# TOP.net
KiCad netlist of a schematic drawn in Altium Designer
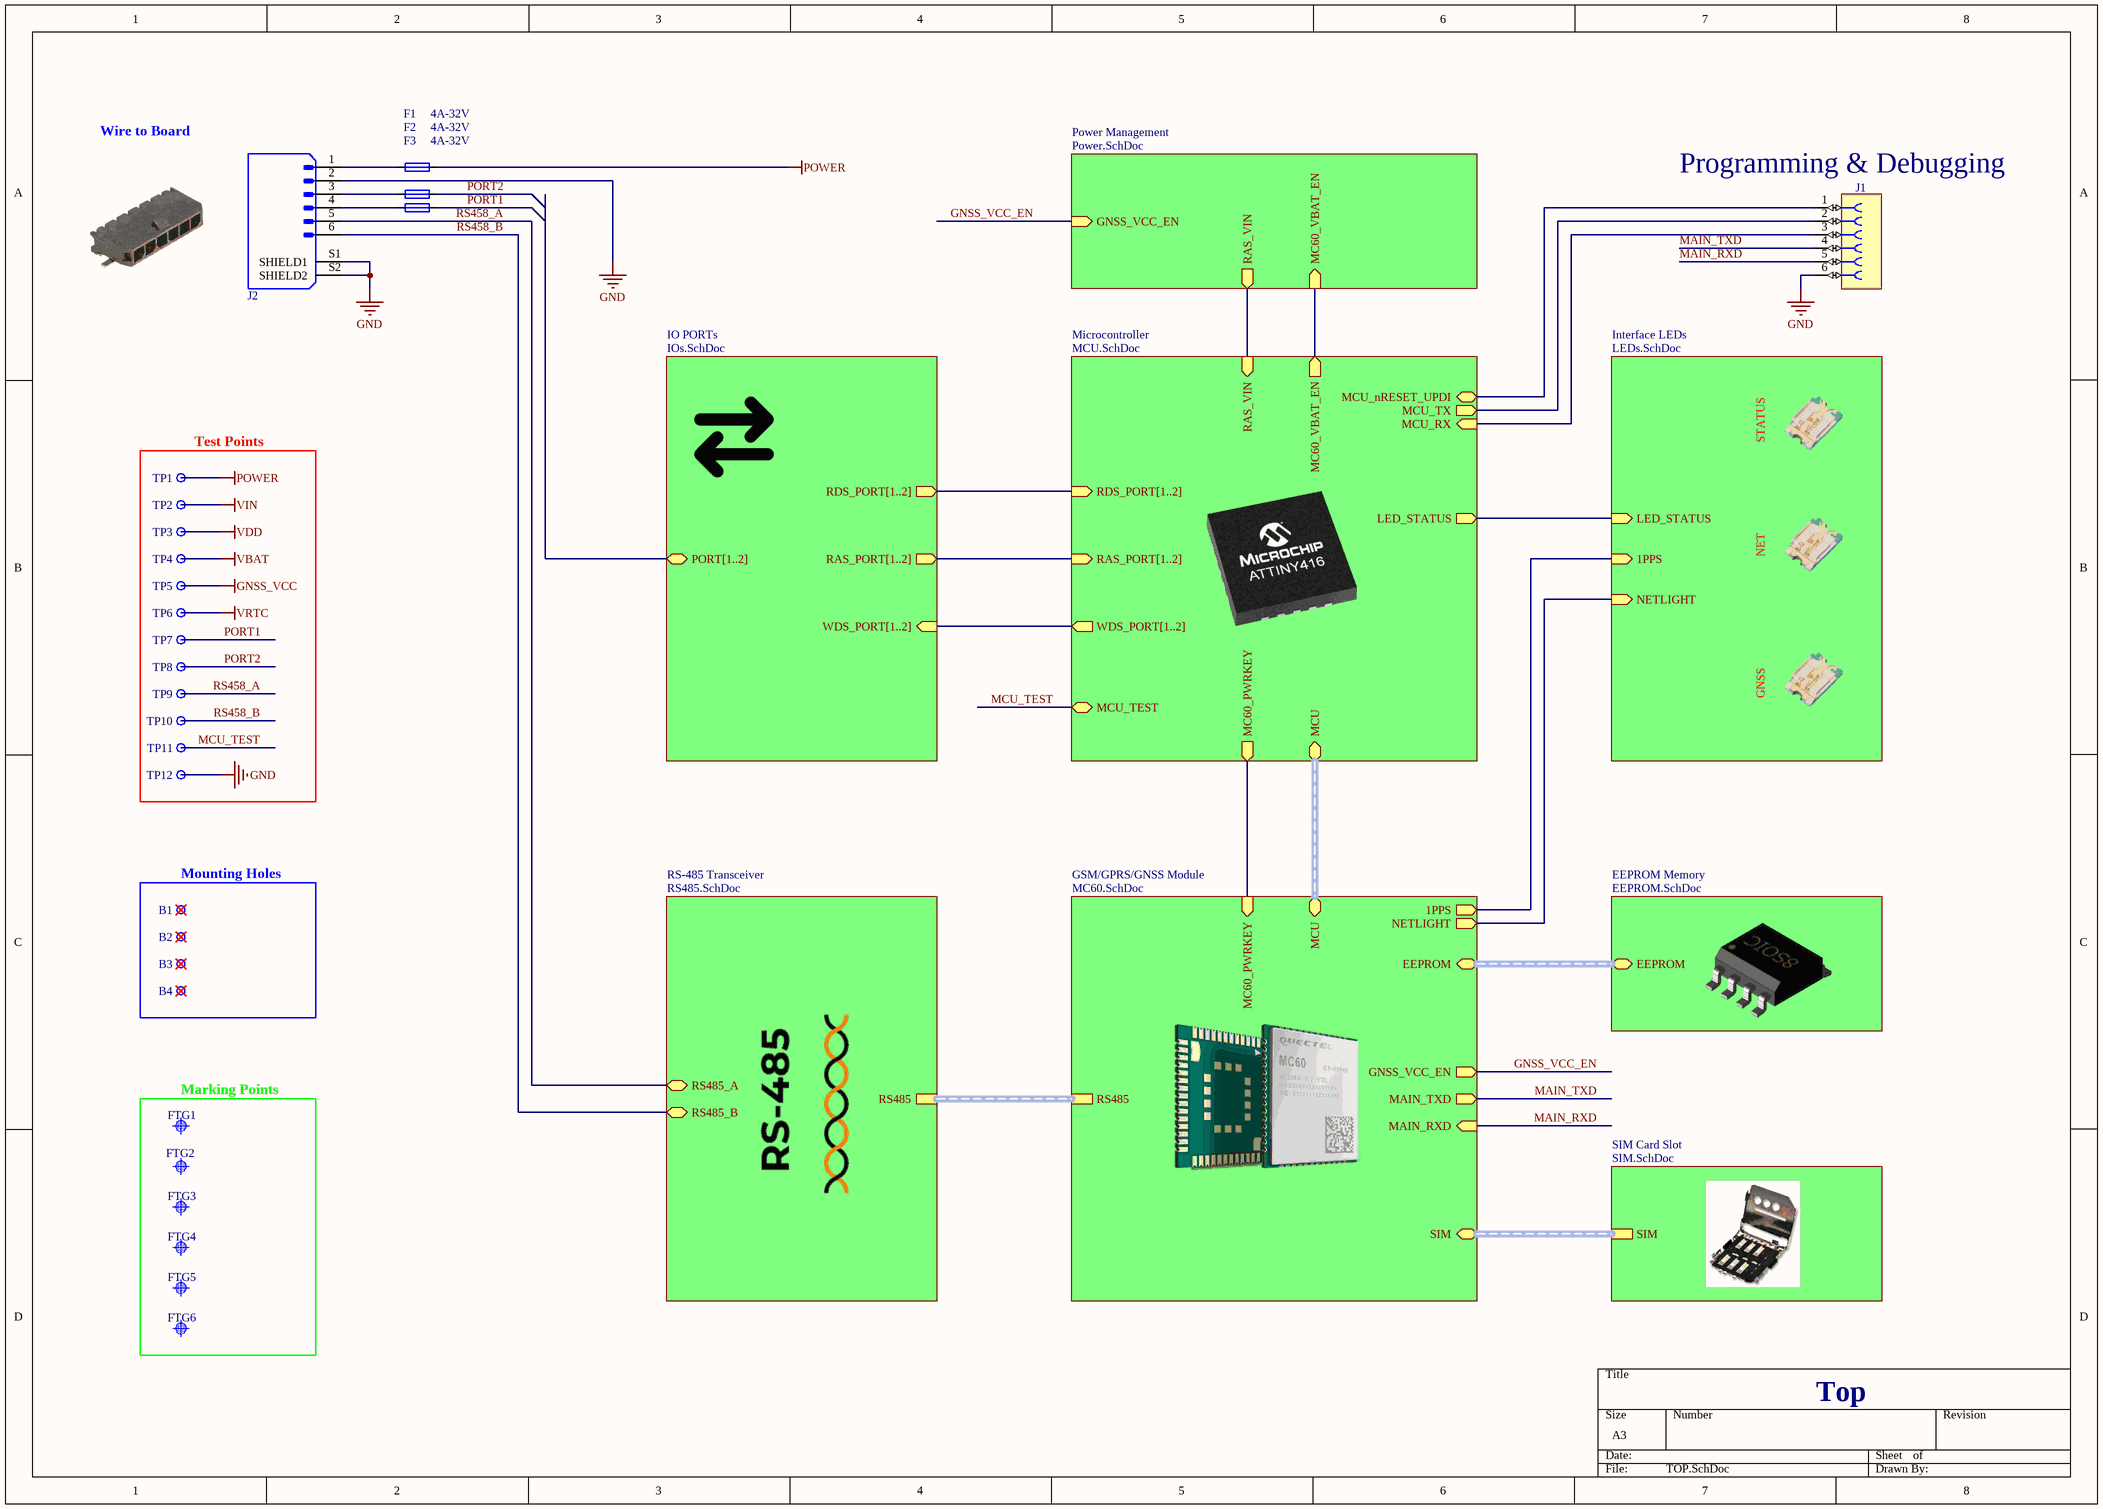
[diagram p0: TOP.SchDoc]

(export (version "E")
  (design (tool "Eeschema 10.0.6"))
  (components
    (comp (ref "B1")
      (value "Non Plated Hole")
      (footprint "MTG520")
      (description "Single Terminal Socket")
      (fields (field (name "PART NUMBER") "NON-PLATED_HOLE5.2") (field (name "AUTHOR") "CERN DEM JMW"))
      (libsource (lib "Eletro-mechanical") (part "Single Terminal Socket"))
    )
    (comp (ref "B2")
      (value "Non Plated Hole")
      (footprint "MTG520")
      (description "Single Terminal Socket")
      (fields (field (name "PART NUMBER") "NON-PLATED_HOLE5.2") (field (name "AUTHOR") "CERN DEM JMW"))
      (libsource (lib "Eletro-mechanical") (part "Single Terminal Socket"))
    )
    (comp (ref "B3")
      (value "Non Plated Hole")
      (footprint "MTG520")
      (description "Single Terminal Socket")
      (fields (field (name "PART NUMBER") "NON-PLATED_HOLE5.2") (field (name "AUTHOR") "CERN DEM JMW"))
      (libsource (lib "Eletro-mechanical") (part "Single Terminal Socket"))
    )
    (comp (ref "B4")
      (value "Non Plated Hole")
      (footprint "MTG520")
      (description "Single Terminal Socket")
      (fields (field (name "PART NUMBER") "NON-PLATED_HOLE5.2") (field (name "AUTHOR") "CERN DEM JMW"))
      (libsource (lib "Eletro-mechanical") (part "Single Terminal Socket"))
    )
    (comp (ref "F1")
      (value "4A-32V")
      (footprint "FUSC_LITTELFUSE_466")
      (description "Fuse")
      (fields
        (field (name "PART NUMBER") "FUS1206_LITTELFUSE_0466004.NR")
        (field (name "MANUFACTURER") "LITTELFUSE")
        (field (name "AUTHOR") "CERN DEM BC")
      )
      (libsource (lib "Eletro-mechanical") (part "Fuse"))
    )
    (comp (ref "F2")
      (value "4A-32V")
      (footprint "FUSC_LITTELFUSE_466")
      (description "Fuse")
      (fields
        (field (name "PART NUMBER") "FUS1206_LITTELFUSE_0466004.NR")
        (field (name "MANUFACTURER") "LITTELFUSE")
        (field (name "AUTHOR") "CERN DEM BC")
      )
      (libsource (lib "Eletro-mechanical") (part "Fuse"))
    )
    (comp (ref "F3")
      (value "4A-32V")
      (footprint "FUSC_LITTELFUSE_466")
      (description "Fuse")
      (fields
        (field (name "PART NUMBER") "FUS1206_LITTELFUSE_0466004.NR")
        (field (name "MANUFACTURER") "LITTELFUSE")
        (field (name "AUTHOR") "CERN DEM BC")
      )
      (libsource (lib "Eletro-mechanical") (part "Fuse"))
    )
    (comp (ref "FTG1")
      (value "Use only in PCB")
      (footprint "FIDUCIAL_TOP_C100-200")
      (description "Fiducial Target")
      (fields (field (name "PART NUMBER") "FIDUCIAL_TARGET_C100-200") (field (name "AUTHOR") "CERN DEM JLC"))
      (libsource (lib "Eletro-mechanical") (part "Fiducial Target"))
    )
    (comp (ref "FTG2")
      (value "Use only in PCB")
      (footprint "FIDUCIAL_TOP_C100-200")
      (description "Fiducial Target")
      (fields (field (name "PART NUMBER") "FIDUCIAL_TARGET_C100-200") (field (name "AUTHOR") "CERN DEM JLC"))
      (libsource (lib "Eletro-mechanical") (part "Fiducial Target"))
    )
    (comp (ref "FTG3")
      (value "Use only in PCB")
      (footprint "FIDUCIAL_TOP_C100-200")
      (description "Fiducial Target")
      (fields (field (name "PART NUMBER") "FIDUCIAL_TARGET_C100-200") (field (name "AUTHOR") "CERN DEM JLC"))
      (libsource (lib "Eletro-mechanical") (part "Fiducial Target"))
    )
    (comp (ref "FTG4")
      (value "Use only in PCB")
      (footprint "FIDUCIAL_TOP_C100-200")
      (description "Fiducial Target")
      (fields (field (name "PART NUMBER") "FIDUCIAL_TARGET_C100-200") (field (name "AUTHOR") "CERN DEM JLC"))
      (libsource (lib "Eletro-mechanical") (part "Fiducial Target"))
    )
    (comp (ref "FTG5")
      (value "Use only in PCB")
      (footprint "FIDUCIAL_TOP_C100-200")
      (description "Fiducial Target")
      (fields (field (name "PART NUMBER") "FIDUCIAL_TARGET_C100-200") (field (name "AUTHOR") "CERN DEM JLC"))
      (libsource (lib "Eletro-mechanical") (part "Fiducial Target"))
    )
    (comp (ref "FTG6")
      (value "Use only in PCB")
      (footprint "FIDUCIAL_TOP_C100-200")
      (description "Fiducial Target")
      (fields (field (name "PART NUMBER") "FIDUCIAL_TARGET_C100-200") (field (name "AUTHOR") "CERN DEM JLC"))
      (libsource (lib "Eletro-mechanical") (part "Fiducial Target"))
    )
    (comp (ref "J1")
      (value "Socket 6")
      (footprint "SAMTEC_SSW-106-01-L-S")
      (description "Connector 6 Female")
      (fields
        (field (name "PART NUMBER") "SAMTEC_SSW-106-01-L-S")
        (field (name "MANUFACTURER") "OPEN")
        (field (name "AUTHOR") "CERN DEM BC")
      )
      (libsource (lib "Connectors") (part "Connector 6 Female"))
    )
    (comp (ref "J2")
      (value "43650-0613")
      (footprint "MOLEX_43650-0613")
      (description "Connector Header Surface Mount, Right Angle 6 position 0.118\" (3.00mm)")
      (fields
        (field (name "MP") "436500613")
        (field (name "PART NUMBER") "MOLEX_43650-0613")
        (field (name "AUTHOR") "Xusniyor")
      )
      (libsource (lib "Connectors") (part "MOLEX_43650-0613"))
    )
    (comp (ref "TP1")
      (value "Test Point")
      (footprint "TPS127")
      (fields (field (name "PART NUMBER") "SMD_PAD_1.27X1.27MM") (field (name "AUTHOR") "CERN DEM JLC"))
      (libsource (lib "Eletro-mechanical") (part "Test Point"))
    )
    (comp (ref "TP2")
      (value "Test Point")
      (footprint "TPS127")
      (fields (field (name "PART NUMBER") "SMD_PAD_1.27X1.27MM") (field (name "AUTHOR") "CERN DEM JLC"))
      (libsource (lib "Eletro-mechanical") (part "Test Point"))
    )
    (comp (ref "TP3")
      (value "Test Point")
      (footprint "TPS127")
      (fields (field (name "PART NUMBER") "SMD_PAD_1.27X1.27MM") (field (name "AUTHOR") "CERN DEM JLC"))
      (libsource (lib "Eletro-mechanical") (part "Test Point"))
    )
    (comp (ref "TP4")
      (value "Test Point")
      (footprint "TPS127")
      (fields (field (name "PART NUMBER") "SMD_PAD_1.27X1.27MM") (field (name "AUTHOR") "CERN DEM JLC"))
      (libsource (lib "Eletro-mechanical") (part "Test Point"))
    )
    (comp (ref "TP5")
      (value "Test Point")
      (footprint "TPS127")
      (fields (field (name "PART NUMBER") "SMD_PAD_1.27X1.27MM") (field (name "AUTHOR") "CERN DEM JLC"))
      (libsource (lib "Eletro-mechanical") (part "Test Point"))
    )
    (comp (ref "TP6")
      (value "Test Point")
      (footprint "TPS127")
      (fields (field (name "PART NUMBER") "SMD_PAD_1.27X1.27MM") (field (name "AUTHOR") "CERN DEM JLC"))
      (libsource (lib "Eletro-mechanical") (part "Test Point"))
    )
    (comp (ref "TP7")
      (value "Test Point")
      (footprint "TPS127")
      (fields (field (name "PART NUMBER") "SMD_PAD_1.27X1.27MM") (field (name "AUTHOR") "CERN DEM JLC"))
      (libsource (lib "Eletro-mechanical") (part "Test Point"))
    )
    (comp (ref "TP8")
      (value "Test Point")
      (footprint "TPS127")
      (fields (field (name "PART NUMBER") "SMD_PAD_1.27X1.27MM") (field (name "AUTHOR") "CERN DEM JLC"))
      (libsource (lib "Eletro-mechanical") (part "Test Point"))
    )
    (comp (ref "TP9")
      (value "Test Point")
      (footprint "TPS127")
      (fields (field (name "PART NUMBER") "SMD_PAD_1.27X1.27MM") (field (name "AUTHOR") "CERN DEM JLC"))
      (libsource (lib "Eletro-mechanical") (part "Test Point"))
    )
    (comp (ref "TP10")
      (value "Test Point")
      (footprint "TPS127")
      (fields (field (name "PART NUMBER") "SMD_PAD_1.27X1.27MM") (field (name "AUTHOR") "CERN DEM JLC"))
      (libsource (lib "Eletro-mechanical") (part "Test Point"))
    )
    (comp (ref "TP11")
      (value "Test Point")
      (footprint "TPS127")
      (fields (field (name "PART NUMBER") "SMD_PAD_1.27X1.27MM") (field (name "AUTHOR") "CERN DEM JLC"))
      (libsource (lib "Eletro-mechanical") (part "Test Point"))
    )
    (comp (ref "TP12")
      (value "Test Point")
      (footprint "TPS127")
      (fields (field (name "PART NUMBER") "SMD_PAD_1.27X1.27MM") (field (name "AUTHOR") "CERN DEM JLC"))
      (libsource (lib "Eletro-mechanical") (part "Test Point"))
    )
  )
  (nets
    (net (code "5") (name "/MAIN_RXD") (class "Default")
      (node (ref "J1") (pin "5") (pinfunction "5_5") (pintype "bidirectional"))
    )
    (net (code "6") (name "/MAIN_TXD") (class "Default")
      (node (ref "J1") (pin "4") (pinfunction "4_4") (pintype "bidirectional"))
    )
    (net (code "9") (name "/MCU_RX") (class "Default")
      (node (ref "J1") (pin "3") (pinfunction "3_3") (pintype "bidirectional"))
    )
    (net (code "10") (name "/MCU_TEST") (class "Default")
      (node (ref "TP11") (pin "1") (pinfunction "1_1") (pintype "bidirectional"))
    )
    (net (code "11") (name "/MCU_TX") (class "Default")
      (node (ref "J1") (pin "2") (pinfunction "2_2") (pintype "bidirectional"))
    )
    (net (code "12") (name "/MCU_nRESET_UPDI") (class "Default")
      (node (ref "J1") (pin "1") (pinfunction "1_1") (pintype "bidirectional"))
    )
    (net (code "15") (name "/PORT1") (class "Default")
      (node (ref "F3") (pin "2") (pinfunction "2_2") (pintype "passive"))
      (node (ref "TP7") (pin "1") (pinfunction "1_1") (pintype "bidirectional"))
    )
    (net (code "16") (name "/PORT2") (class "Default")
      (node (ref "F2") (pin "2") (pinfunction "2_2") (pintype "passive"))
      (node (ref "TP8") (pin "1") (pinfunction "1_1") (pintype "bidirectional"))
    )
    (net (code "21") (name "/RS458_A") (class "Default")
      (node (ref "J2") (pin "5") (pinfunction "5_5") (pintype "passive"))
      (node (ref "TP9") (pin "1") (pinfunction "1_1") (pintype "bidirectional"))
    )
    (net (code "22") (name "/RS458_B") (class "Default")
      (node (ref "J2") (pin "6") (pinfunction "6_6") (pintype "passive"))
      (node (ref "TP10") (pin "1") (pinfunction "1_1") (pintype "bidirectional"))
    )
    (net (code "26") (name "GND") (class "Default")
      (node (ref "J1") (pin "6") (pinfunction "6_6") (pintype "bidirectional"))
      (node (ref "J2") (pin "2") (pinfunction "2_2") (pintype "passive"))
      (node (ref "J2") (pin "S1") (pinfunction "SHIELD1_S1") (pintype "passive"))
      (node (ref "J2") (pin "S2") (pinfunction "SHIELD2_S2") (pintype "passive"))
      (node (ref "TP12") (pin "1") (pinfunction "1_1") (pintype "bidirectional"))
    )
    (net (code "27") (name "GNSS_VCC") (class "Default")
      (node (ref "TP5") (pin "1") (pinfunction "1_1") (pintype "bidirectional"))
    )
    (net (code "28") (name "Net-(F1-Pad1)") (class "Default")
      (node (ref "F1") (pin "1") (pinfunction "1_1") (pintype "passive"))
      (node (ref "J2") (pin "1") (pinfunction "1_1") (pintype "passive"))
    )
    (net (code "29") (name "Net-(F2-Pad1)") (class "Default")
      (node (ref "F2") (pin "1") (pinfunction "1_1") (pintype "passive"))
      (node (ref "J2") (pin "3") (pinfunction "3_3") (pintype "passive"))
    )
    (net (code "30") (name "Net-(F3-Pad1)") (class "Default")
      (node (ref "F3") (pin "1") (pinfunction "1_1") (pintype "passive"))
      (node (ref "J2") (pin "4") (pinfunction "4_4") (pintype "passive"))
    )
    (net (code "31") (name "POWER") (class "Default")
      (node (ref "F1") (pin "2") (pinfunction "2_2") (pintype "passive"))
      (node (ref "TP1") (pin "1") (pinfunction "1_1") (pintype "bidirectional"))
    )
    (net (code "32") (name "VBAT") (class "Default")
      (node (ref "TP4") (pin "1") (pinfunction "1_1") (pintype "bidirectional"))
    )
    (net (code "33") (name "VDD") (class "Default")
      (node (ref "TP3") (pin "1") (pinfunction "1_1") (pintype "bidirectional"))
    )
    (net (code "34") (name "VIN") (class "Default")
      (node (ref "TP2") (pin "1") (pinfunction "1_1") (pintype "bidirectional"))
    )
    (net (code "35") (name "VRTC") (class "Default")
      (node (ref "TP6") (pin "1") (pinfunction "1_1") (pintype "bidirectional"))
    )
    (net (code "36") (name "unconnected-(B1-Pad1)") (class "Default")
      (node (ref "B1") (pin "1") (pinfunction "1_1") (pintype "bidirectional+no_connect"))
    )
    (net (code "37") (name "unconnected-(B2-Pad1)") (class "Default")
      (node (ref "B2") (pin "1") (pinfunction "1_1") (pintype "bidirectional+no_connect"))
    )
    (net (code "38") (name "unconnected-(B3-Pad1)") (class "Default")
      (node (ref "B3") (pin "1") (pinfunction "1_1") (pintype "bidirectional+no_connect"))
    )
    (net (code "39") (name "unconnected-(B4-Pad1)") (class "Default")
      (node (ref "B4") (pin "1") (pinfunction "1_1") (pintype "bidirectional+no_connect"))
    )
  )
)
